# enc_as5047p.net
KiCad netlist of a schematic drawn in EAGLE
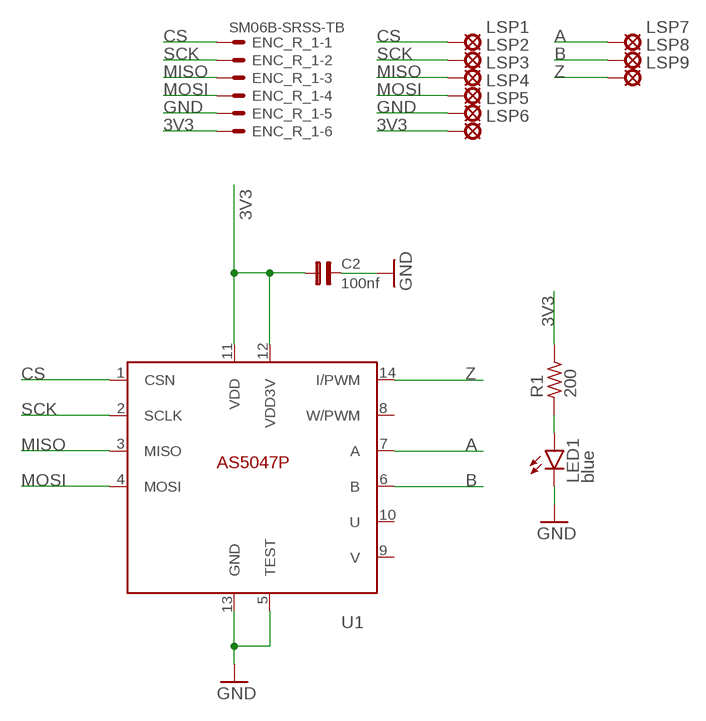
[diagram p0: schematic, sheet 1]

(export (version "E")
  (design (tool "Eeschema 10.0.6"))
  (components
    (comp (ref "C2")
      (value "100nf")
      (footprint "eagle-import:0603")
      (libsource (lib "eagle-import") (part "C0603"))
    )
    (comp (ref "ENC_R_1")
      (value "SM06B-SRSS-TB")
      (footprint "eagle-import:SM06B-SRSS-TB")
      (libsource (lib "eagle-import") (part "?M06B-SRSS-TBS"))
    )
    (comp (ref "LED1")
      (value "blue")
      (footprint "eagle-import:SML0603")
      (libsource (lib "eagle-import") (part "LEDSML0603"))
    )
    (comp (ref "LSP1")
      (value "LSP10")
      (footprint "eagle-import:LSP10")
      (libsource (lib "eagle-import") (part "LSP10"))
    )
    (comp (ref "LSP2")
      (value "LSP10")
      (footprint "eagle-import:LSP10")
      (libsource (lib "eagle-import") (part "LSP10"))
    )
    (comp (ref "LSP3")
      (value "LSP10")
      (footprint "eagle-import:LSP10")
      (libsource (lib "eagle-import") (part "LSP10"))
    )
    (comp (ref "LSP4")
      (value "LSP10")
      (footprint "eagle-import:LSP10")
      (libsource (lib "eagle-import") (part "LSP10"))
    )
    (comp (ref "LSP5")
      (value "LSP10")
      (footprint "eagle-import:LSP10")
      (libsource (lib "eagle-import") (part "LSP10"))
    )
    (comp (ref "LSP6")
      (value "LSP10")
      (footprint "eagle-import:LSP10")
      (libsource (lib "eagle-import") (part "LSP10"))
    )
    (comp (ref "LSP7")
      (value "LSP10")
      (footprint "eagle-import:LSP10")
      (libsource (lib "eagle-import") (part "LSP10"))
    )
    (comp (ref "LSP8")
      (value "LSP10")
      (footprint "eagle-import:LSP10")
      (libsource (lib "eagle-import") (part "LSP10"))
    )
    (comp (ref "LSP9")
      (value "LSP10")
      (footprint "eagle-import:LSP10")
      (libsource (lib "eagle-import") (part "LSP10"))
    )
    (comp (ref "R1")
      (value "200")
      (footprint "eagle-import:R0603")
      (libsource (lib "eagle-import") (part "R_0603"))
    )
    (comp (ref "U1")
      (value "AS5047P")
      (footprint "eagle-import:TSSOP14")
      (libsource (lib "eagle-import") (part "AS5047P"))
    )
  )
  (nets
    (net (code "1") (name "/3V3") (class "Default")
      (node (ref "C2") (pin "1") (pinfunction "1_1") (pintype "passive"))
      (node (ref "ENC_R_1") (pin "6") (pinfunction "S_6") (pintype "passive"))
      (node (ref "LSP6") (pin "MP") (pinfunction "MP_MP") (pintype "passive"))
      (node (ref "R1") (pin "2") (pinfunction "2_2") (pintype "passive"))
      (node (ref "U1") (pin "11") (pinfunction "VDD_11") (pintype "power_in"))
      (node (ref "U1") (pin "12") (pinfunction "VDD3V_12") (pintype "power_in"))
    )
    (net (code "2") (name "/A") (class "Default")
      (node (ref "LSP7") (pin "MP") (pinfunction "MP_MP") (pintype "passive"))
      (node (ref "U1") (pin "7") (pinfunction "A_7") (pintype "output"))
    )
    (net (code "3") (name "/B") (class "Default")
      (node (ref "LSP8") (pin "MP") (pinfunction "MP_MP") (pintype "passive"))
      (node (ref "U1") (pin "6") (pinfunction "B_6") (pintype "output"))
    )
    (net (code "4") (name "/CS") (class "Default")
      (node (ref "ENC_R_1") (pin "1") (pinfunction "S_1") (pintype "passive"))
      (node (ref "LSP1") (pin "MP") (pinfunction "MP_MP") (pintype "passive"))
      (node (ref "U1") (pin "1") (pinfunction "CSN_1") (pintype "input"))
    )
    (net (code "5") (name "/MISO") (class "Default")
      (node (ref "ENC_R_1") (pin "3") (pinfunction "S_3") (pintype "passive"))
      (node (ref "LSP3") (pin "MP") (pinfunction "MP_MP") (pintype "passive"))
      (node (ref "U1") (pin "3") (pinfunction "MISO_3") (pintype "output"))
    )
    (net (code "6") (name "/MOSI") (class "Default")
      (node (ref "ENC_R_1") (pin "4") (pinfunction "S_4") (pintype "passive"))
      (node (ref "LSP4") (pin "MP") (pinfunction "MP_MP") (pintype "passive"))
      (node (ref "U1") (pin "4") (pinfunction "MOSI_4") (pintype "input"))
    )
    (net (code "7") (name "/SCK") (class "Default")
      (node (ref "ENC_R_1") (pin "2") (pinfunction "S_2") (pintype "passive"))
      (node (ref "LSP2") (pin "MP") (pinfunction "MP_MP") (pintype "passive"))
      (node (ref "U1") (pin "2") (pinfunction "SCLK_2") (pintype "input"))
    )
    (net (code "8") (name "/Z") (class "Default")
      (node (ref "LSP9") (pin "MP") (pinfunction "MP_MP") (pintype "passive"))
      (node (ref "U1") (pin "14") (pinfunction "I/PWM_14") (pintype "output"))
    )
    (net (code "9") (name "GND") (class "Default")
      (node (ref "C2") (pin "2") (pinfunction "2_2") (pintype "passive"))
      (node (ref "ENC_R_1") (pin "5") (pinfunction "S_5") (pintype "passive"))
      (node (ref "LED1") (pin "C") (pinfunction "C_C") (pintype "passive"))
      (node (ref "LSP5") (pin "MP") (pinfunction "MP_MP") (pintype "passive"))
      (node (ref "U1") (pin "13") (pinfunction "GND_13") (pintype "power_in"))
      (node (ref "U1") (pin "5") (pinfunction "TEST_5") (pintype "power_in"))
    )
    (net (code "10") (name "Net-(LED1-PadA)") (class "Default")
      (node (ref "LED1") (pin "A") (pinfunction "A_A") (pintype "passive"))
      (node (ref "R1") (pin "1") (pinfunction "1_1") (pintype "passive"))
    )
    (net (code "11") (name "unconnected-(U1-U-Pad10)") (class "Default")
      (node (ref "U1") (pin "10") (pinfunction "U_10") (pintype "output"))
    )
    (net (code "12") (name "unconnected-(U1-V-Pad9)") (class "Default")
      (node (ref "U1") (pin "9") (pinfunction "V_9") (pintype "output"))
    )
    (net (code "13") (name "unconnected-(U1-W{slash}PWM-Pad8)") (class "Default")
      (node (ref "U1") (pin "8") (pinfunction "W/PWM_8") (pintype "output"))
    )
  )
)
